# STM32_Sensors.net
KiCad netlist of a schematic drawn in Altium Designer
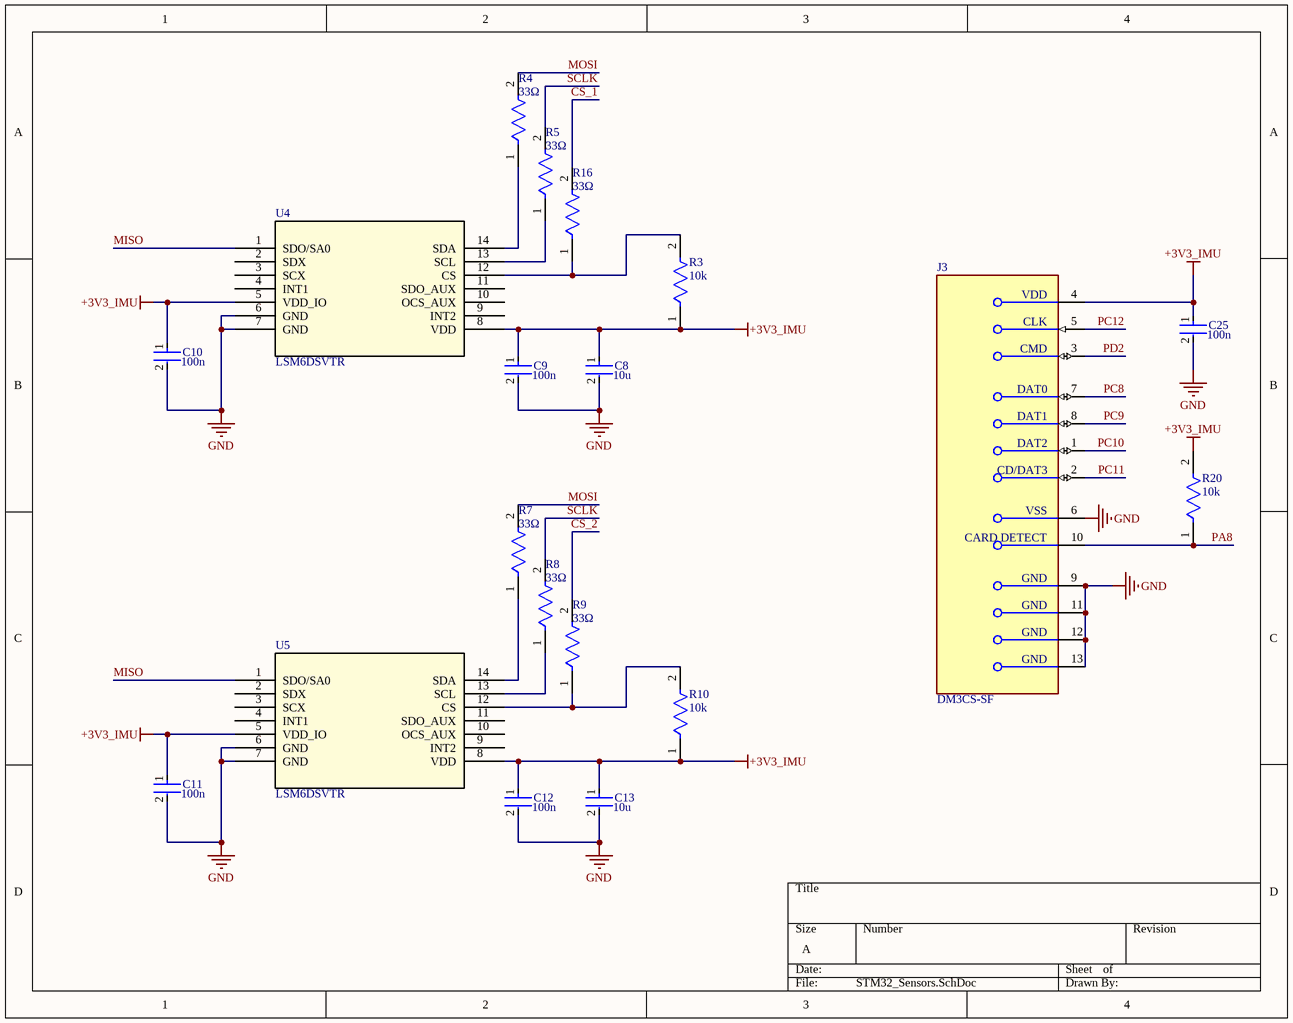
[diagram p0: STM32_Sensors.SchDoc]

(export (version "E")
  (design (tool "Eeschema 10.0.6"))
  (components
    (comp (ref "C8")
      (value "CC0603KRX5R7BB106")
      (footprint "FP-CC0603-DC-MFG")
      (description "CC0603KRX5R7BB106 Multilayer Ceramic Capacitor, 10 uF, 16 V, ± 10%, X5R, 0603 [1608 Metric]")
      (fields (field (name "CAPACITANCE") "10u") (field (name "TOLERANCE") "10%"))
      (libsource (lib "Altium Content Vault") (part "b4654b650e69147ec39a6b967a45e02"))
    )
    (comp (ref "C9")
      (value "0603B104K250CT")
      (footprint "FP-0603B104K250CT-IPC_C")
      (description "CAP CER 0.1UF 25V X7R 0603")
      (fields (field (name "TOLERANCE") "10%") (field (name "CAPACITANCE") "100n"))
      (libsource (lib "Altium Content Vault") (part "b4654b650e69147ec39a6b967a45e02"))
    )
    (comp (ref "C10")
      (value "0603B104K250CT")
      (footprint "FP-0603B104K250CT-IPC_C")
      (description "CAP CER 0.1UF 25V X7R 0603")
      (fields (field (name "TOLERANCE") "10%") (field (name "CAPACITANCE") "100n"))
      (libsource (lib "Altium Content Vault") (part "b4654b650e69147ec39a6b967a45e02"))
    )
    (comp (ref "C11")
      (value "0603B104K250CT")
      (footprint "FP-0603B104K250CT-IPC_C")
      (description "CAP CER 0.1UF 25V X7R 0603")
      (fields (field (name "TOLERANCE") "10%") (field (name "CAPACITANCE") "100n"))
      (libsource (lib "Altium Content Vault") (part "b4654b650e69147ec39a6b967a45e02"))
    )
    (comp (ref "C12")
      (value "0603B104K250CT")
      (footprint "FP-0603B104K250CT-IPC_C")
      (description "CAP CER 0.1UF 25V X7R 0603")
      (fields (field (name "TOLERANCE") "10%") (field (name "CAPACITANCE") "100n"))
      (libsource (lib "Altium Content Vault") (part "b4654b650e69147ec39a6b967a45e02"))
    )
    (comp (ref "C13")
      (value "CC0603KRX5R7BB106")
      (footprint "FP-CC0603-DC-MFG")
      (description "CC0603KRX5R7BB106 Multilayer Ceramic Capacitor, 10 uF, 16 V, ± 10%, X5R, 0603 [1608 Metric]")
      (fields (field (name "CAPACITANCE") "10u") (field (name "TOLERANCE") "10%"))
      (libsource (lib "Altium Content Vault") (part "b4654b650e69147ec39a6b967a45e02"))
    )
    (comp (ref "C25")
      (value "0603B104K250CT")
      (footprint "FP-0603B104K250CT-IPC_C")
      (description "CAP CER 0.1UF 25V X7R 0603")
      (fields (field (name "TOLERANCE") "10%") (field (name "CAPACITANCE") "100n"))
      (libsource (lib "Altium Content Vault") (part "b4654b650e69147ec39a6b967a45e02"))
    )
    (comp (ref "J3")
      (value "DM3CS-SF")
      (footprint "FP-DM3CS-SF-MFG")
      (description "CONN MICRO SD CARD HINGED TYPE")
      (libsource (lib "Altium Content Vault") (part "bac915de5305cfdd1ca301aae530106"))
    )
    (comp (ref "R3")
      (value "10k")
      (footprint "FP-AC0603-IPC_A")
      (description "RES 10kΩ 5.00% 0.2W 0603")
      (fields (field (name "Comment") "AC0603JR-7W10KL"))
      (libsource (lib "Altium Content Vault") (part "1029c3af85768c4190bb7ad29bc67b5"))
    )
    (comp (ref "R4")
      (value "33Ω")
      (footprint "FP-SR0603-MFG")
      (description "RES 33 OHM 1% 1/4W 0603")
      (fields
        (field (name "MANUFACTURER") "Yageo")
        (field (name "MANUFACTURER PART NUMBER") "SR0603FR-7T33RL")
      )
      (libsource (lib "Altium Content Vault") (part "1029c3af85768c4190bb7ad29bc67b5"))
    )
    (comp (ref "R5")
      (value "SR0603FR-7T33RL")
      (footprint "FP-SR0603-MFG")
      (description "RES 33 OHM 1% 1/4W 0603")
      (fields
        (field (name "MANUFACTURER") "Yageo")
        (field (name "RESISTANCE") "33Ω")
        (field (name "OCTOPART") "https://octopart.com/sr0603fr-7t33rl-yageo-92673856")
      )
      (libsource (lib "Altium Content Vault") (part "1029c3af85768c4190bb7ad29bc67b5"))
    )
    (comp (ref "R7")
      (value "33Ω")
      (footprint "FP-SR0603-MFG")
      (description "RES 33 OHM 1% 1/4W 0603")
      (fields
        (field (name "MANUFACTURER") "Yageo")
        (field (name "MANUFACTURER PART NUMBER") "SR0603FR-7T33RL")
      )
      (libsource (lib "Altium Content Vault") (part "1029c3af85768c4190bb7ad29bc67b5"))
    )
    (comp (ref "R8")
      (value "SR0603FR-7T33RL")
      (footprint "FP-SR0603-MFG")
      (description "RES 33 OHM 1% 1/4W 0603")
      (fields
        (field (name "MANUFACTURER") "Yageo")
        (field (name "RESISTANCE") "33Ω")
        (field (name "OCTOPART") "https://octopart.com/sr0603fr-7t33rl-yageo-92673856")
      )
      (libsource (lib "Altium Content Vault") (part "1029c3af85768c4190bb7ad29bc67b5"))
    )
    (comp (ref "R9")
      (value "33Ω")
      (footprint "FP-SR0603-MFG")
      (description "RES 33 OHM 1% 1/4W 0603")
      (fields
        (field (name "MANUFACTURER") "Yageo")
        (field (name "MANUFACTURER PART NUMBER") "SR0603FR-7T33RL")
      )
      (libsource (lib "Altium Content Vault") (part "1029c3af85768c4190bb7ad29bc67b5"))
    )
    (comp (ref "R10")
      (value "10k")
      (footprint "FP-AC0603-IPC_A")
      (description "RES 10kΩ 5.00% 0.2W 0603")
      (fields (field (name "Comment") "AC0603JR-7W10KL"))
      (libsource (lib "Altium Content Vault") (part "1029c3af85768c4190bb7ad29bc67b5"))
    )
    (comp (ref "R16")
      (value "33Ω")
      (footprint "FP-SR0603-MFG")
      (description "RES 33 OHM 1% 1/4W 0603")
      (fields
        (field (name "MANUFACTURER") "Yageo")
        (field (name "MANUFACTURER PART NUMBER") "SR0603FR-7T33RL")
      )
      (libsource (lib "Altium Content Vault") (part "1029c3af85768c4190bb7ad29bc67b5"))
    )
    (comp (ref "R20")
      (value "10k")
      (footprint "FP-AC0603-IPC_A")
      (description "RES 10kΩ 5.00% 0.2W 0603")
      (fields (field (name "Comment") "AC0603JR-7W10KL"))
      (libsource (lib "Altium Content Vault") (part "1029c3af85768c4190bb7ad29bc67b5"))
    )
    (comp (ref "U4")
      (value "LSM6DSVTR")
      (footprint "LGA14-L_2P59X3P1X0P5_STM")
      (description "6-axis IMU with embedded sensor fusion, I3C, OIS/EIS for smart applications")
      (fields (field (name "COPYRIGHT") "Copyright (C) 2026 Ultra Librarian. All rights reserved."))
      (libsource (lib "Schlib1") (part "LSM6DSVTR"))
    )
    (comp (ref "U5")
      (value "LSM6DSVTR")
      (footprint "LGA14-L_2P59X3P1X0P5_STM")
      (description "6-axis IMU with embedded sensor fusion, I3C, OIS/EIS for smart applications")
      (fields (field (name "COPYRIGHT") "Copyright (C) 2026 Ultra Librarian. All rights reserved."))
      (libsource (lib "Schlib1") (part "LSM6DSVTR"))
    )
  )
  (nets
    (net (code "1") (name "+3V3_IMU") (class "Default")
      (node (ref "C10") (pin "1") (pinfunction "1_1") (pintype "passive"))
      (node (ref "C11") (pin "1") (pinfunction "1_1") (pintype "passive"))
      (node (ref "C12") (pin "1") (pinfunction "1_1") (pintype "passive"))
      (node (ref "C13") (pin "1") (pinfunction "1_1") (pintype "passive"))
      (node (ref "C25") (pin "1") (pinfunction "1_1") (pintype "passive"))
      (node (ref "C8") (pin "1") (pinfunction "1_1") (pintype "passive"))
      (node (ref "C9") (pin "1") (pinfunction "1_1") (pintype "passive"))
      (node (ref "J3") (pin "4") (pinfunction "VDD_4") (pintype "power_in"))
      (node (ref "R10") (pin "1") (pinfunction "1_1") (pintype "passive"))
      (node (ref "R20") (pin "2") (pinfunction "2_2") (pintype "passive"))
      (node (ref "R3") (pin "1") (pinfunction "1_1") (pintype "passive"))
      (node (ref "U4") (pin "5") (pinfunction "VDD_IO_5") (pintype "power_in"))
      (node (ref "U4") (pin "8") (pinfunction "VDD_8") (pintype "power_in"))
      (node (ref "U5") (pin "5") (pinfunction "VDD_IO_5") (pintype "power_in"))
      (node (ref "U5") (pin "8") (pinfunction "VDD_8") (pintype "power_in"))
    )
    (net (code "2") (name "/CS_1") (class "Default")
      (node (ref "R16") (pin "2") (pinfunction "2_2") (pintype "passive"))
    )
    (net (code "3") (name "/CS_2") (class "Default")
      (node (ref "R9") (pin "2") (pinfunction "2_2") (pintype "passive"))
    )
    (net (code "4") (name "/MISO") (class "Default")
      (node (ref "U4") (pin "1") (pinfunction "SDO/SA0_1") (pintype "passive"))
      (node (ref "U5") (pin "1") (pinfunction "SDO/SA0_1") (pintype "passive"))
    )
    (net (code "5") (name "/MOSI") (class "Default")
      (node (ref "R4") (pin "2") (pinfunction "2_2") (pintype "passive"))
      (node (ref "R7") (pin "2") (pinfunction "2_2") (pintype "passive"))
    )
    (net (code "6") (name "/PA8") (class "Default")
      (node (ref "J3") (pin "10") (pinfunction "CARD_DETECT_10") (pintype "passive"))
      (node (ref "R20") (pin "1") (pinfunction "1_1") (pintype "passive"))
    )
    (net (code "7") (name "/PC8") (class "Default")
      (node (ref "J3") (pin "7") (pinfunction "DAT0_7") (pintype "bidirectional"))
    )
    (net (code "8") (name "/PC9") (class "Default")
      (node (ref "J3") (pin "8") (pinfunction "DAT1_8") (pintype "bidirectional"))
    )
    (net (code "9") (name "/PC10") (class "Default")
      (node (ref "J3") (pin "1") (pinfunction "DAT2_1") (pintype "bidirectional"))
    )
    (net (code "10") (name "/PC11") (class "Default")
      (node (ref "J3") (pin "2") (pinfunction "CD/DAT3_2") (pintype "bidirectional"))
    )
    (net (code "11") (name "/PC12") (class "Default")
      (node (ref "J3") (pin "5") (pinfunction "CLK_5") (pintype "input"))
    )
    (net (code "12") (name "/PD2") (class "Default")
      (node (ref "J3") (pin "3") (pinfunction "CMD_3") (pintype "bidirectional"))
    )
    (net (code "13") (name "/SCLK") (class "Default")
      (node (ref "R5") (pin "2") (pinfunction "2_2") (pintype "passive"))
      (node (ref "R8") (pin "2") (pinfunction "2_2") (pintype "passive"))
    )
    (net (code "14") (name "GND") (class "Default")
      (node (ref "C10") (pin "2") (pinfunction "2_2") (pintype "passive"))
      (node (ref "C11") (pin "2") (pinfunction "2_2") (pintype "passive"))
      (node (ref "C12") (pin "2") (pinfunction "2_2") (pintype "passive"))
      (node (ref "C13") (pin "2") (pinfunction "2_2") (pintype "passive"))
      (node (ref "C25") (pin "2") (pinfunction "2_2") (pintype "passive"))
      (node (ref "C8") (pin "2") (pinfunction "2_2") (pintype "passive"))
      (node (ref "C9") (pin "2") (pinfunction "2_2") (pintype "passive"))
      (node (ref "J3") (pin "11") (pinfunction "GND_11") (pintype "power_in"))
      (node (ref "J3") (pin "12") (pinfunction "GND_12") (pintype "power_in"))
      (node (ref "J3") (pin "13") (pinfunction "GND_13") (pintype "power_in"))
      (node (ref "J3") (pin "6") (pinfunction "VSS_6") (pintype "power_in"))
      (node (ref "J3") (pin "9") (pinfunction "GND_9") (pintype "power_in"))
      (node (ref "U4") (pin "6") (pinfunction "GND_6") (pintype "power_in"))
      (node (ref "U4") (pin "7") (pinfunction "GND_7") (pintype "power_in"))
      (node (ref "U5") (pin "6") (pinfunction "GND_6") (pintype "power_in"))
      (node (ref "U5") (pin "7") (pinfunction "GND_7") (pintype "power_in"))
    )
    (net (code "15") (name "Net-(U4-CS)") (class "Default")
      (node (ref "R16") (pin "1") (pinfunction "1_1") (pintype "passive"))
      (node (ref "R3") (pin "2") (pinfunction "2_2") (pintype "passive"))
      (node (ref "U4") (pin "12") (pinfunction "CS_12") (pintype "passive"))
    )
    (net (code "16") (name "Net-(U4-SCL)") (class "Default")
      (node (ref "R5") (pin "1") (pinfunction "1_1") (pintype "passive"))
      (node (ref "U4") (pin "13") (pinfunction "SCL_13") (pintype "passive"))
    )
    (net (code "17") (name "Net-(U4-SDA)") (class "Default")
      (node (ref "R4") (pin "1") (pinfunction "1_1") (pintype "passive"))
      (node (ref "U4") (pin "14") (pinfunction "SDA_14") (pintype "passive"))
    )
    (net (code "18") (name "Net-(U5-CS)") (class "Default")
      (node (ref "R10") (pin "2") (pinfunction "2_2") (pintype "passive"))
      (node (ref "R9") (pin "1") (pinfunction "1_1") (pintype "passive"))
      (node (ref "U5") (pin "12") (pinfunction "CS_12") (pintype "passive"))
    )
    (net (code "19") (name "Net-(U5-SCL)") (class "Default")
      (node (ref "R8") (pin "1") (pinfunction "1_1") (pintype "passive"))
      (node (ref "U5") (pin "13") (pinfunction "SCL_13") (pintype "passive"))
    )
    (net (code "20") (name "Net-(U5-SDA)") (class "Default")
      (node (ref "R7") (pin "1") (pinfunction "1_1") (pintype "passive"))
      (node (ref "U5") (pin "14") (pinfunction "SDA_14") (pintype "passive"))
    )
    (net (code "21") (name "unconnected-(U4-INT1-Pad4)") (class "Default")
      (node (ref "U4") (pin "4") (pinfunction "INT1_4") (pintype "passive"))
    )
    (net (code "22") (name "unconnected-(U4-INT2-Pad9)") (class "Default")
      (node (ref "U4") (pin "9") (pinfunction "INT2_9") (pintype "passive"))
    )
    (net (code "23") (name "unconnected-(U4-OCS_AUX-Pad10)") (class "Default")
      (node (ref "U4") (pin "10") (pinfunction "OCS_AUX_10") (pintype "passive"))
    )
    (net (code "24") (name "unconnected-(U4-SCX-Pad3)") (class "Default")
      (node (ref "U4") (pin "3") (pinfunction "SCX_3") (pintype "passive"))
    )
    (net (code "25") (name "unconnected-(U4-SDO_AUX-Pad11)") (class "Default")
      (node (ref "U4") (pin "11") (pinfunction "SDO_AUX_11") (pintype "passive"))
    )
    (net (code "26") (name "unconnected-(U4-SDX-Pad2)") (class "Default")
      (node (ref "U4") (pin "2") (pinfunction "SDX_2") (pintype "passive"))
    )
    (net (code "27") (name "unconnected-(U5-INT1-Pad4)") (class "Default")
      (node (ref "U5") (pin "4") (pinfunction "INT1_4") (pintype "passive"))
    )
    (net (code "28") (name "unconnected-(U5-INT2-Pad9)") (class "Default")
      (node (ref "U5") (pin "9") (pinfunction "INT2_9") (pintype "passive"))
    )
    (net (code "29") (name "unconnected-(U5-OCS_AUX-Pad10)") (class "Default")
      (node (ref "U5") (pin "10") (pinfunction "OCS_AUX_10") (pintype "passive"))
    )
    (net (code "30") (name "unconnected-(U5-SCX-Pad3)") (class "Default")
      (node (ref "U5") (pin "3") (pinfunction "SCX_3") (pintype "passive"))
    )
    (net (code "31") (name "unconnected-(U5-SDO_AUX-Pad11)") (class "Default")
      (node (ref "U5") (pin "11") (pinfunction "SDO_AUX_11") (pintype "passive"))
    )
    (net (code "32") (name "unconnected-(U5-SDX-Pad2)") (class "Default")
      (node (ref "U5") (pin "2") (pinfunction "SDX_2") (pintype "passive"))
    )
  )
)
